# SCH_PS2_Floppy_MediaSense_Adapter_2024-0.net
KiCad netlist of a schematic drawn in EasyEDA
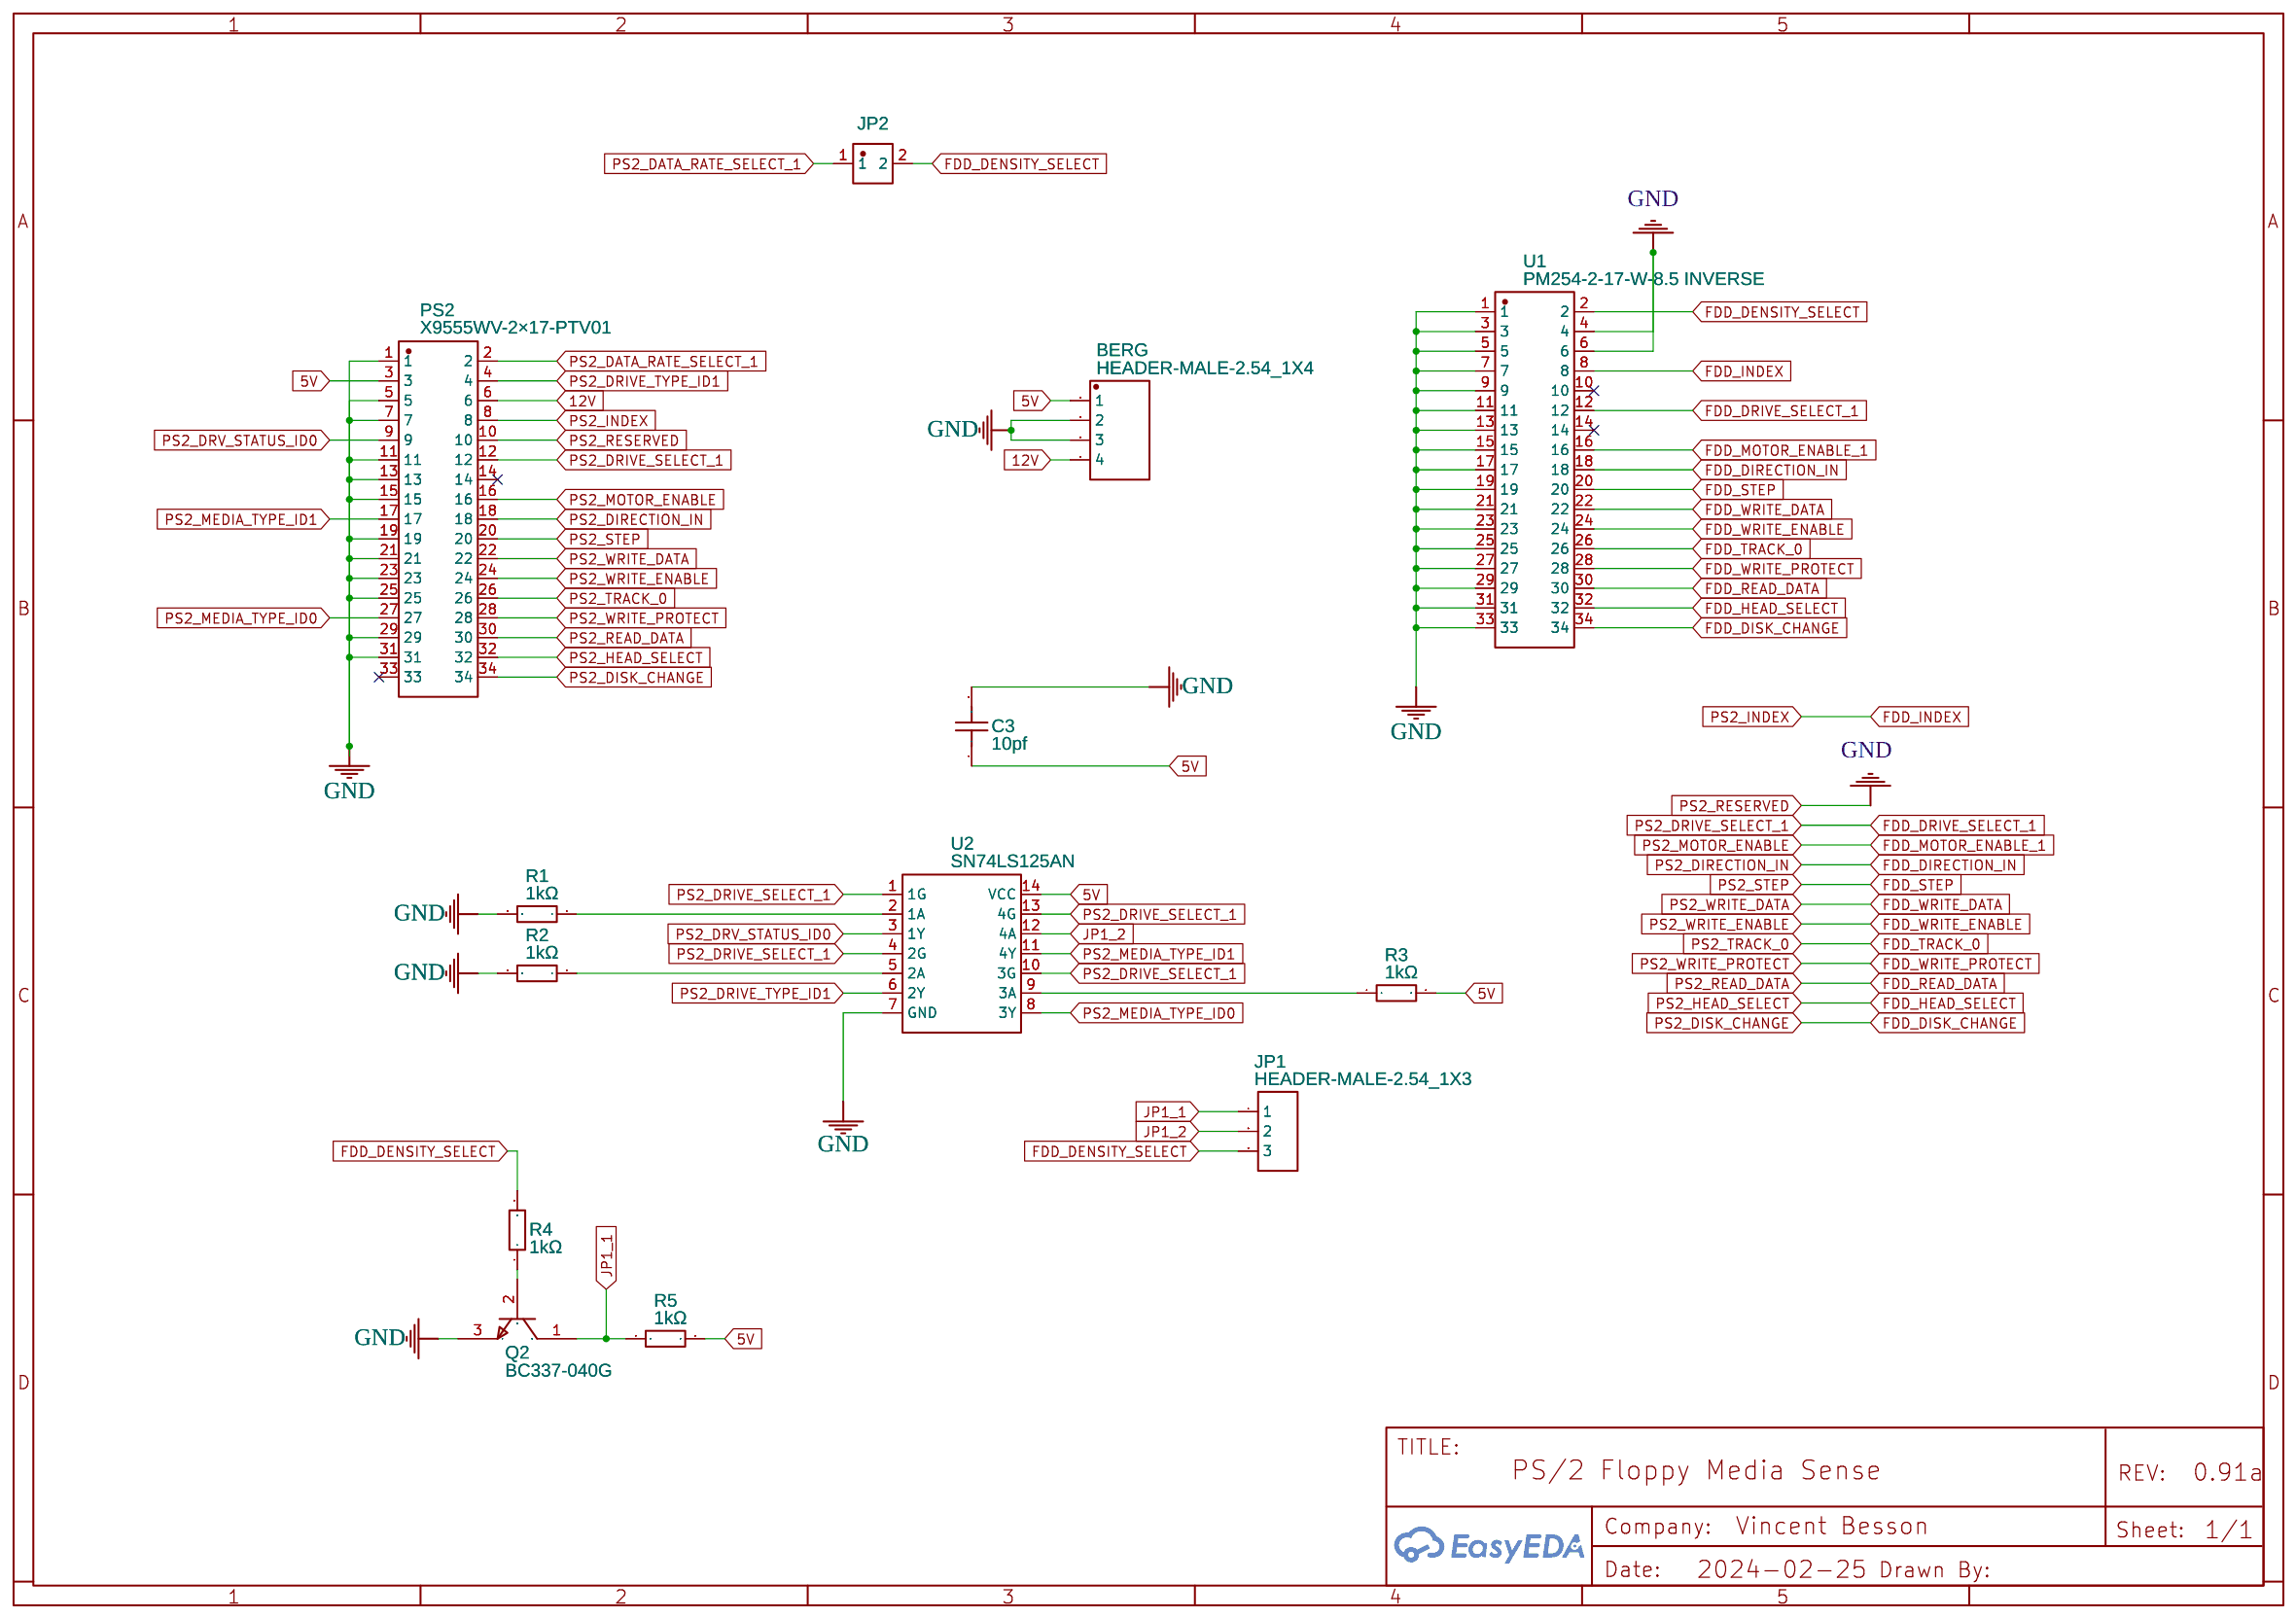
[diagram p0: schematic sheet]

(export (version "E")
  (design (tool "Eeschema 10.0.6"))
  (components
    (comp (ref "BERG")
      (value "HEADER-MALE-2.54_1X4")
      (fields
        (field (name "Manufacturer Part") "210S-1*4P L=11.6MMGold-plated black")
        (field (name "Manufacturer") "Ckmtw")
      )
      (libsource (lib "") (part "HEADER-MALE-2.54_1X4"))
    )
    (comp (ref "C3")
      (value "10pf")
      (fields
        (field (name "Manufacturer Part") "CC1H200KA1PDCH4B3003")
        (field (name "Manufacturer") "Dersonic(德尔创)")
      )
      (libsource (lib "") (part "CC1H200KA1PDCH4B3003"))
    )
    (comp (ref "JP1")
      (value "HEADER-MALE-2.54_1X3")
      (fields (field (name "Manufacturer Part") "Header2.54mm 1*3P") (field (name "Manufacturer") "BOOMELE"))
      (libsource (lib "") (part "HEADER-MALE-2.54_1X3"))
    )
    (comp (ref "JP2")
      (value "GAZPAR")
      (fields
        (field (name "Manufacturer Part") "X6521WV-2x01H-C30D60")
        (field (name "Manufacturer") "XKB Connectivity(中国星坤)")
      )
      (libsource (lib "") (part "X6521WV-2X01H-C30D60"))
    )
    (comp (ref "PS2")
      (value "X9555WV-2×17-PTV01")
      (fields
        (field (name "Manufacturer Part") "X9555WV-2x17-PTV01")
        (field (name "Manufacturer") "XKB Connectivity(中国星坤)")
      )
      (libsource (lib "") (part "X9555WV-2×17-PTV01"))
    )
    (comp (ref "Q2") (value "BC337-040G") (libsource (lib "") (part "BC337-040G")))
    (comp (ref "R1")
      (value "1kΩ")
      (fields
        (field (name "Manufacturer Part") "MFR0W4F1002A50")
        (field (name "Manufacturer") "UNI-ROYAL(厚声)")
      )
      (libsource (lib "") (part "MFR0W4F1002A50"))
    )
    (comp (ref "R2")
      (value "1kΩ")
      (fields
        (field (name "Manufacturer Part") "MFR0W4F1002A50")
        (field (name "Manufacturer") "UNI-ROYAL(厚声)")
      )
      (libsource (lib "") (part "MFR0W4F1002A50"))
    )
    (comp (ref "R3")
      (value "1kΩ")
      (fields
        (field (name "Manufacturer Part") "MFR0W4F1002A50")
        (field (name "Manufacturer") "UNI-ROYAL(厚声)")
      )
      (libsource (lib "") (part "MFR0W4F1002A50_1"))
    )
    (comp (ref "R4")
      (value "1kΩ")
      (fields
        (field (name "Manufacturer Part") "MFR0W4F1002A50")
        (field (name "Manufacturer") "UNI-ROYAL(厚声)")
      )
      (libsource (lib "") (part "MFR0W4F1002A50_2"))
    )
    (comp (ref "R5")
      (value "1kΩ")
      (fields
        (field (name "Manufacturer Part") "MFR0W4F1002A50")
        (field (name "Manufacturer") "UNI-ROYAL(厚声)")
      )
      (libsource (lib "") (part "MFR0W4F1002A50_1"))
    )
    (comp (ref "U1")
      (value "PM254-2-17-W-8.5 INVERSE")
      (fields
        (field (name "Manufacturer Part") "PM254-2-17-W-8.5")
        (field (name "Manufacturer") "HCTL(华灿天禄)")
      )
      (libsource (lib "") (part "PM254-2-17-W-8.5 INVERSE"))
    )
    (comp (ref "U2") (value "SN74LS125AN") (libsource (lib "") (part "SN74LS125AN")))
  )
  (nets
    (net (code "1") (name "5V") (class "Default")
      (node (ref "BERG") (pin "1") (pinfunction "1_1") (pintype "unspecified"))
      (node (ref "C3") (pin "1") (pinfunction "1_1") (pintype "unspecified"))
      (node (ref "PS2") (pin "3") (pinfunction "3_3") (pintype "unspecified"))
      (node (ref "R3") (pin "2") (pinfunction "2_2") (pintype "input"))
      (node (ref "R5") (pin "2") (pinfunction "2_2") (pintype "input"))
      (node (ref "U2") (pin "14") (pinfunction "VCC_14") (pintype "passive"))
    )
    (net (code "2") (name "12V") (class "Default")
      (node (ref "BERG") (pin "4") (pinfunction "4_4") (pintype "unspecified"))
      (node (ref "PS2") (pin "6") (pinfunction "6_6") (pintype "unspecified"))
    )
    (net (code "3") (name "FDD_DENSITY_SELECT") (class "Default")
      (node (ref "JP1") (pin "3") (pinfunction "3_3") (pintype "input"))
      (node (ref "JP2") (pin "2") (pinfunction "2_2") (pintype "unspecified"))
      (node (ref "R4") (pin "2") (pinfunction "2_2") (pintype "input"))
      (node (ref "U1") (pin "2") (pinfunction "2_2") (pintype "unspecified"))
    )
    (net (code "4") (name "FDD_DIRECTION_IN") (class "Default")
      (node (ref "PS2") (pin "18") (pinfunction "18_18") (pintype "unspecified"))
      (node (ref "U1") (pin "18") (pinfunction "18_18") (pintype "unspecified"))
    )
    (net (code "5") (name "FDD_DISK_CHANGE") (class "Default")
      (node (ref "PS2") (pin "34") (pinfunction "34_34") (pintype "unspecified"))
      (node (ref "U1") (pin "34") (pinfunction "34_34") (pintype "unspecified"))
    )
    (net (code "6") (name "FDD_DRIVE_SELECT_1") (class "Default")
      (node (ref "PS2") (pin "12") (pinfunction "12_12") (pintype "unspecified"))
      (node (ref "U1") (pin "12") (pinfunction "12_12") (pintype "unspecified"))
      (node (ref "U2") (pin "1") (pinfunction "1G_1") (pintype "unspecified"))
      (node (ref "U2") (pin "10") (pinfunction "3G_10") (pintype "unspecified"))
      (node (ref "U2") (pin "13") (pinfunction "4G_13") (pintype "unspecified"))
      (node (ref "U2") (pin "4") (pinfunction "2G_4") (pintype "unspecified"))
    )
    (net (code "7") (name "FDD_HEAD_SELECT") (class "Default")
      (node (ref "PS2") (pin "32") (pinfunction "32_32") (pintype "unspecified"))
      (node (ref "U1") (pin "32") (pinfunction "32_32") (pintype "unspecified"))
    )
    (net (code "8") (name "FDD_INDEX") (class "Default")
      (node (ref "PS2") (pin "8") (pinfunction "8_8") (pintype "unspecified"))
      (node (ref "U1") (pin "8") (pinfunction "8_8") (pintype "unspecified"))
    )
    (net (code "9") (name "FDD_MOTOR_ENABLE_1") (class "Default")
      (node (ref "PS2") (pin "16") (pinfunction "16_16") (pintype "unspecified"))
      (node (ref "U1") (pin "16") (pinfunction "16_16") (pintype "unspecified"))
    )
    (net (code "10") (name "FDD_READ_DATA") (class "Default")
      (node (ref "PS2") (pin "30") (pinfunction "30_30") (pintype "unspecified"))
      (node (ref "U1") (pin "30") (pinfunction "30_30") (pintype "unspecified"))
    )
    (net (code "11") (name "FDD_STEP") (class "Default")
      (node (ref "PS2") (pin "20") (pinfunction "20_20") (pintype "unspecified"))
      (node (ref "U1") (pin "20") (pinfunction "20_20") (pintype "unspecified"))
    )
    (net (code "12") (name "FDD_TRACK_0") (class "Default")
      (node (ref "PS2") (pin "26") (pinfunction "26_26") (pintype "unspecified"))
      (node (ref "U1") (pin "26") (pinfunction "26_26") (pintype "unspecified"))
    )
    (net (code "13") (name "FDD_WRITE_DATA") (class "Default")
      (node (ref "PS2") (pin "22") (pinfunction "22_22") (pintype "unspecified"))
      (node (ref "U1") (pin "22") (pinfunction "22_22") (pintype "unspecified"))
    )
    (net (code "14") (name "FDD_WRITE_ENABLE") (class "Default")
      (node (ref "PS2") (pin "24") (pinfunction "24_24") (pintype "unspecified"))
      (node (ref "U1") (pin "24") (pinfunction "24_24") (pintype "unspecified"))
    )
    (net (code "15") (name "FDD_WRITE_PROTECT") (class "Default")
      (node (ref "PS2") (pin "28") (pinfunction "28_28") (pintype "unspecified"))
      (node (ref "U1") (pin "28") (pinfunction "28_28") (pintype "unspecified"))
    )
    (net (code "16") (name "JP1_1") (class "Default")
      (node (ref "JP1") (pin "1") (pinfunction "1_1") (pintype "input"))
      (node (ref "Q2") (pin "1") (pinfunction "C_1") (pintype "unspecified"))
      (node (ref "R5") (pin "1") (pinfunction "1_1") (pintype "input"))
    )
    (net (code "17") (name "JP1_2") (class "Default")
      (node (ref "JP1") (pin "2") (pinfunction "2_2") (pintype "input"))
      (node (ref "U2") (pin "12") (pinfunction "4A_12") (pintype "unspecified"))
    )
    (net (code "18") (name "Net-(Q2-B)") (class "Default")
      (node (ref "Q2") (pin "2") (pinfunction "B_2") (pintype "unspecified"))
      (node (ref "R4") (pin "1") (pinfunction "1_1") (pintype "input"))
    )
    (net (code "19") (name "Net-(U2-1A)") (class "Default")
      (node (ref "R1") (pin "1") (pinfunction "1_1") (pintype "input"))
      (node (ref "U2") (pin "2") (pinfunction "1A_2") (pintype "unspecified"))
    )
    (net (code "20") (name "Net-(U2-2A)") (class "Default")
      (node (ref "R2") (pin "1") (pinfunction "1_1") (pintype "input"))
      (node (ref "U2") (pin "5") (pinfunction "2A_5") (pintype "unspecified"))
    )
    (net (code "21") (name "Net-(U2-3A)") (class "Default")
      (node (ref "R3") (pin "1") (pinfunction "1_1") (pintype "input"))
      (node (ref "U2") (pin "9") (pinfunction "3A_9") (pintype "unspecified"))
    )
    (net (code "22") (name "PS2_DATA_RATE_SELECT_1") (class "Default")
      (node (ref "JP2") (pin "1") (pinfunction "1_1") (pintype "unspecified"))
      (node (ref "PS2") (pin "2") (pinfunction "2_2") (pintype "unspecified"))
    )
    (net (code "23") (name "PS2_DRIVE_TYPE_ID1") (class "Default")
      (node (ref "PS2") (pin "4") (pinfunction "4_4") (pintype "unspecified"))
      (node (ref "U2") (pin "6") (pinfunction "2Y_6") (pintype "unspecified"))
    )
    (net (code "24") (name "PS2_DRV_STATUS_ID0") (class "Default")
      (node (ref "PS2") (pin "9") (pinfunction "9_9") (pintype "unspecified"))
      (node (ref "U2") (pin "3") (pinfunction "1Y_3") (pintype "unspecified"))
    )
    (net (code "25") (name "PS2_MEDIA_TYPE_ID0") (class "Default")
      (node (ref "PS2") (pin "27") (pinfunction "27_27") (pintype "unspecified"))
      (node (ref "U2") (pin "8") (pinfunction "3Y_8") (pintype "unspecified"))
    )
    (net (code "26") (name "PS2_MEDIA_TYPE_ID1") (class "Default")
      (node (ref "PS2") (pin "17") (pinfunction "17_17") (pintype "unspecified"))
      (node (ref "U2") (pin "11") (pinfunction "4Y_11") (pintype "unspecified"))
    )
    (net (code "27") (name "PS2_RESERVED") (class "Default")
      (node (ref "BERG") (pin "2") (pinfunction "2_2") (pintype "unspecified"))
      (node (ref "BERG") (pin "3") (pinfunction "3_3") (pintype "unspecified"))
      (node (ref "C3") (pin "2") (pinfunction "2_2") (pintype "unspecified"))
      (node (ref "PS2") (pin "1") (pinfunction "1_1") (pintype "unspecified"))
      (node (ref "PS2") (pin "10") (pinfunction "10_10") (pintype "unspecified"))
      (node (ref "PS2") (pin "11") (pinfunction "11_11") (pintype "unspecified"))
      (node (ref "PS2") (pin "13") (pinfunction "13_13") (pintype "unspecified"))
      (node (ref "PS2") (pin "15") (pinfunction "15_15") (pintype "unspecified"))
      (node (ref "PS2") (pin "19") (pinfunction "19_19") (pintype "unspecified"))
      (node (ref "PS2") (pin "21") (pinfunction "21_21") (pintype "unspecified"))
      (node (ref "PS2") (pin "23") (pinfunction "23_23") (pintype "unspecified"))
      (node (ref "PS2") (pin "25") (pinfunction "25_25") (pintype "unspecified"))
      (node (ref "PS2") (pin "29") (pinfunction "29_29") (pintype "unspecified"))
      (node (ref "PS2") (pin "31") (pinfunction "31_31") (pintype "unspecified"))
      (node (ref "PS2") (pin "5") (pinfunction "5_5") (pintype "unspecified"))
      (node (ref "PS2") (pin "7") (pinfunction "7_7") (pintype "unspecified"))
      (node (ref "Q2") (pin "3") (pinfunction "E_3") (pintype "unspecified"))
      (node (ref "R1") (pin "2") (pinfunction "2_2") (pintype "input"))
      (node (ref "R2") (pin "2") (pinfunction "2_2") (pintype "input"))
      (node (ref "U1") (pin "1") (pinfunction "1_1") (pintype "unspecified"))
      (node (ref "U1") (pin "11") (pinfunction "11_11") (pintype "unspecified"))
      (node (ref "U1") (pin "13") (pinfunction "13_13") (pintype "unspecified"))
      (node (ref "U1") (pin "15") (pinfunction "15_15") (pintype "unspecified"))
      (node (ref "U1") (pin "17") (pinfunction "17_17") (pintype "unspecified"))
      (node (ref "U1") (pin "19") (pinfunction "19_19") (pintype "unspecified"))
      (node (ref "U1") (pin "21") (pinfunction "21_21") (pintype "unspecified"))
      (node (ref "U1") (pin "23") (pinfunction "23_23") (pintype "unspecified"))
      (node (ref "U1") (pin "25") (pinfunction "25_25") (pintype "unspecified"))
      (node (ref "U1") (pin "27") (pinfunction "27_27") (pintype "unspecified"))
      (node (ref "U1") (pin "29") (pinfunction "29_29") (pintype "unspecified"))
      (node (ref "U1") (pin "3") (pinfunction "3_3") (pintype "unspecified"))
      (node (ref "U1") (pin "31") (pinfunction "31_31") (pintype "unspecified"))
      (node (ref "U1") (pin "33") (pinfunction "33_33") (pintype "unspecified"))
      (node (ref "U1") (pin "4") (pinfunction "4_4") (pintype "unspecified"))
      (node (ref "U1") (pin "5") (pinfunction "5_5") (pintype "unspecified"))
      (node (ref "U1") (pin "6") (pinfunction "6_6") (pintype "unspecified"))
      (node (ref "U1") (pin "7") (pinfunction "7_7") (pintype "unspecified"))
      (node (ref "U1") (pin "9") (pinfunction "9_9") (pintype "unspecified"))
      (node (ref "U2") (pin "7") (pinfunction "GND_7") (pintype "passive"))
    )
    (net (code "28") (name "unconnected-(PS2-Pad14)") (class "Default")
      (node (ref "PS2") (pin "14") (pinfunction "14_14") (pintype "unspecified+no_connect"))
    )
    (net (code "29") (name "unconnected-(PS2-Pad33)") (class "Default")
      (node (ref "PS2") (pin "33") (pinfunction "33_33") (pintype "unspecified+no_connect"))
    )
    (net (code "30") (name "unconnected-(U1-Pad10)") (class "Default")
      (node (ref "U1") (pin "10") (pinfunction "10_10") (pintype "unspecified+no_connect"))
    )
    (net (code "31") (name "unconnected-(U1-Pad14)") (class "Default")
      (node (ref "U1") (pin "14") (pinfunction "14_14") (pintype "unspecified+no_connect"))
    )
  )
)
